# Awesome-Shield-0_5.net
KiCad netlist of a schematic drawn in EAGLE
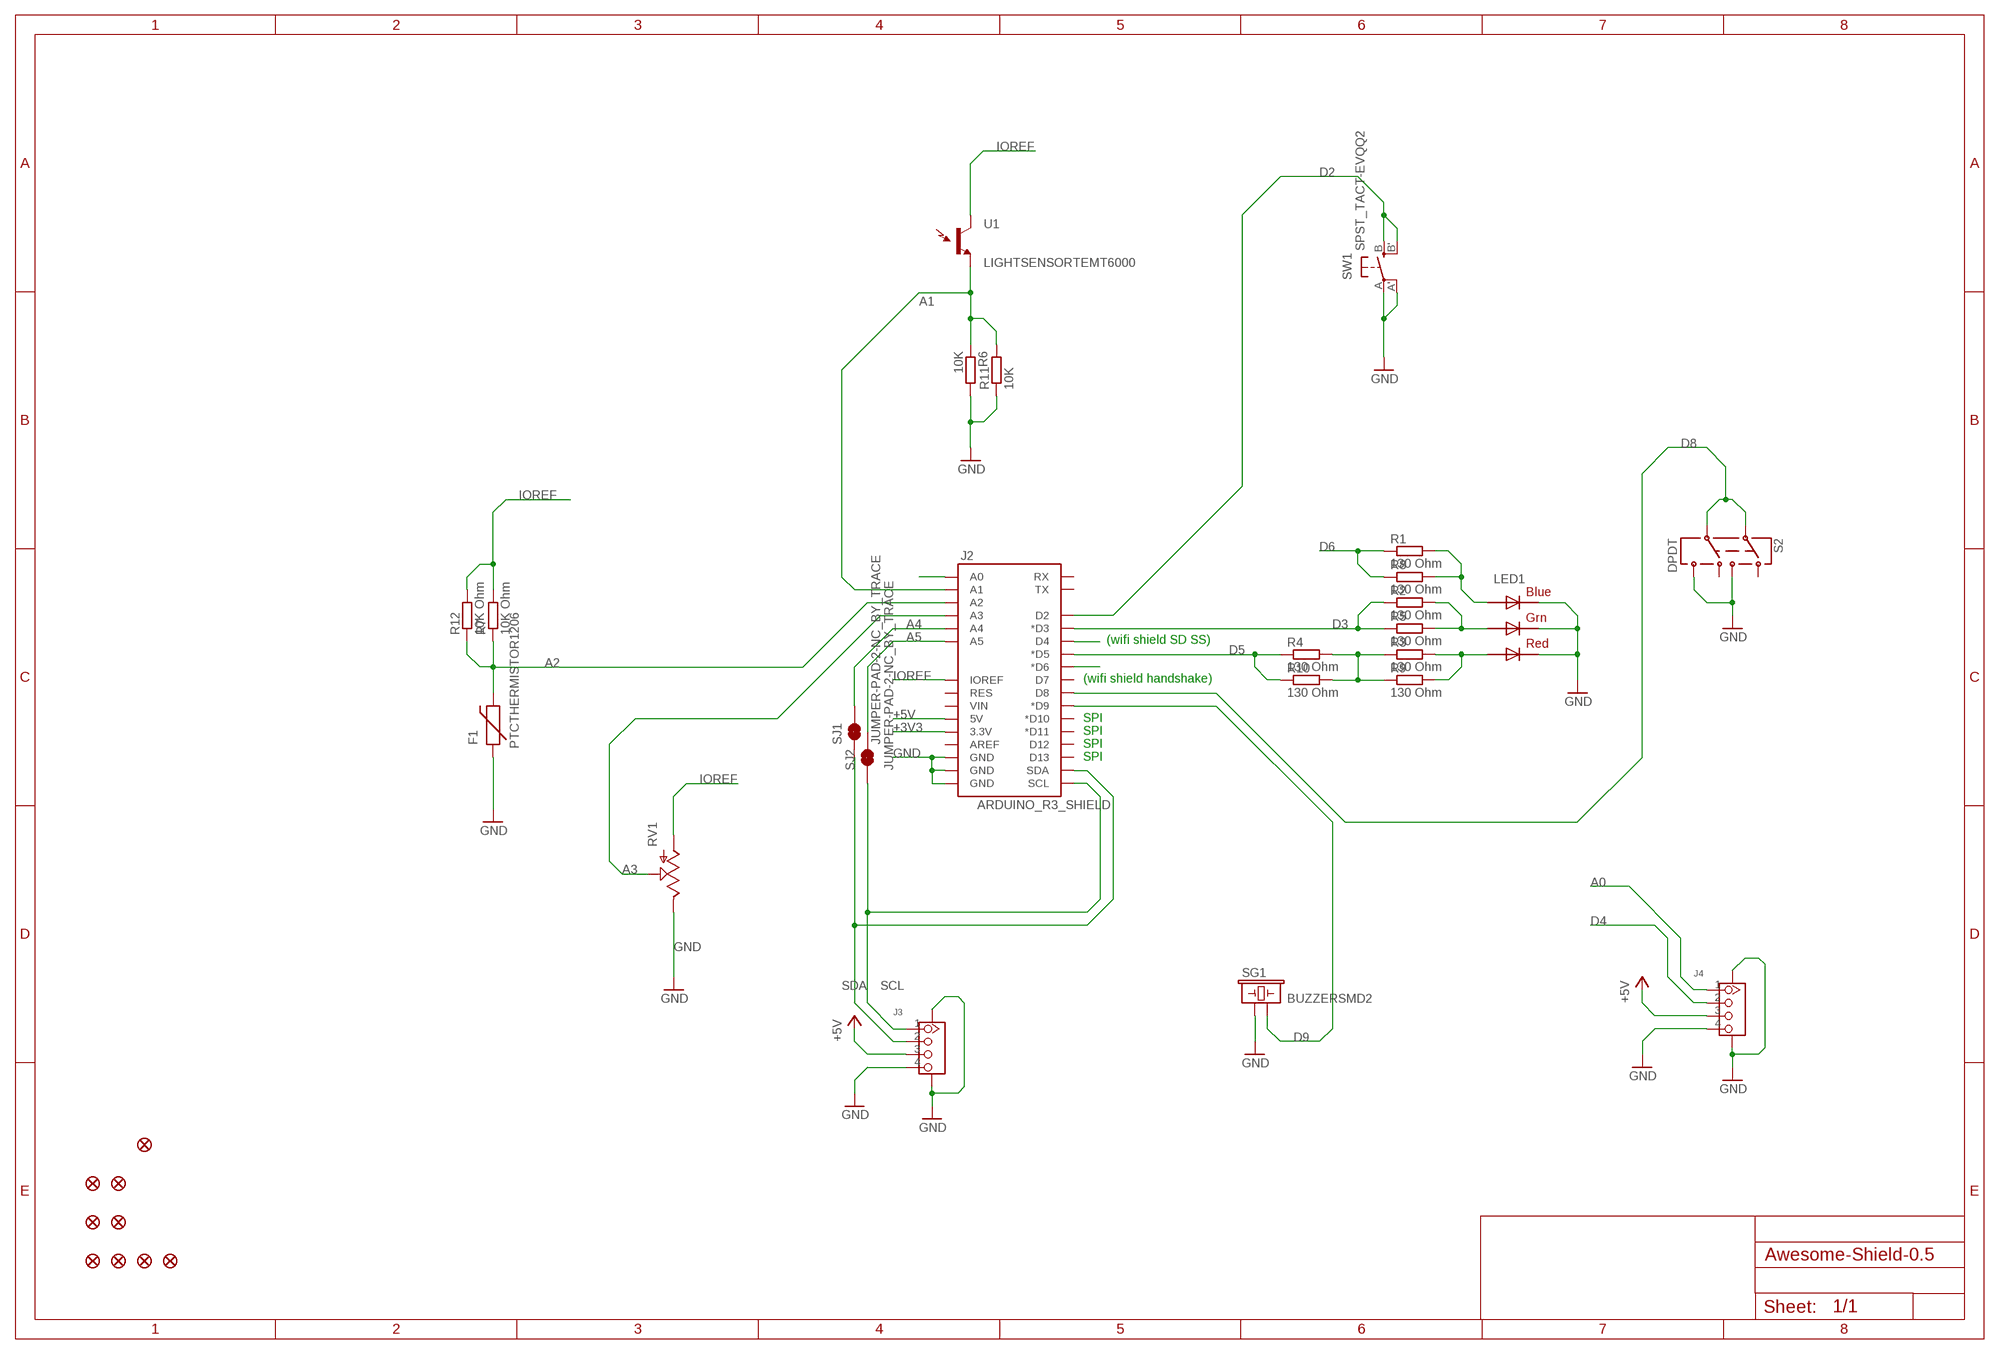
[diagram p0: schematic, sheet 1]

(export (version "E")
  (design (tool "Eeschema 10.0.6"))
  (components
    (comp (ref "F1")
      (value "PTCTHERMISTOR1206")
      (footprint "eagle-import:PTC-1206")
      (libsource (lib "eagle-import") (part "PTCTHERMISTOR1206"))
    )
    (comp (ref "FID1")
      (value "FIDUCIAL1X2")
      (footprint "eagle-import:FIDUCIAL-1X2")
      (libsource (lib "eagle-import") (part "FIDUCIAL1X2"))
    )
    (comp (ref "FID2")
      (value "FIDUCIAL1X2")
      (footprint "eagle-import:FIDUCIAL-1X2")
      (libsource (lib "eagle-import") (part "FIDUCIAL1X2"))
    )
    (comp (ref "FID3")
      (value "FIDUCIAL1X2")
      (footprint "eagle-import:FIDUCIAL-1X2")
      (libsource (lib "eagle-import") (part "FIDUCIAL1X2"))
    )
    (comp (ref "FID4")
      (value "FIDUCIAL1X2")
      (footprint "eagle-import:FIDUCIAL-1X2")
      (libsource (lib "eagle-import") (part "FIDUCIAL1X2"))
    )
    (comp (ref "FID5")
      (value "FIDUCIALUFIDUCIAL")
      (footprint "eagle-import:MICRO-FIDUCIAL")
      (libsource (lib "eagle-import") (part "FIDUCIALUFIDUCIAL"))
    )
    (comp (ref "FID6")
      (value "FIDUCIALUFIDUCIAL")
      (footprint "eagle-import:MICRO-FIDUCIAL")
      (libsource (lib "eagle-import") (part "FIDUCIALUFIDUCIAL"))
    )
    (comp (ref "FID9")
      (value "FIDUCIALUFIDUCIAL")
      (footprint "eagle-import:MICRO-FIDUCIAL")
      (libsource (lib "eagle-import") (part "FIDUCIALUFIDUCIAL"))
    )
    (comp (ref "FID10")
      (value "FIDUCIALUFIDUCIAL")
      (footprint "eagle-import:MICRO-FIDUCIAL")
      (libsource (lib "eagle-import") (part "FIDUCIALUFIDUCIAL"))
    )
    (comp (ref "FID15")
      (value "FIDUCIALUFIDUCIAL")
      (footprint "eagle-import:MICRO-FIDUCIAL")
      (libsource (lib "eagle-import") (part "FIDUCIALUFIDUCIAL"))
    )
    (comp (ref "J2")
      (value "ARDUINO_R3_SHIELD")
      (footprint "eagle-import:UNO_R3_SHIELD")
      (libsource (lib "eagle-import") (part "ARDUINO_R3_SHIELD"))
    )
    (comp (ref "J3")
      (value "GROVE-CONNECTOR-SMD(4+2P-2.0)")
      (footprint "eagle-import:HW4-SMD-2.0")
      (libsource (lib "eagle-import") (part "GROVE-CONNECTOR-SMD(4+2P-2.0)"))
    )
    (comp (ref "J4")
      (value "GROVE-CONNECTOR-SMD(4+2P-2.0)")
      (footprint "eagle-import:HW4-SMD-2.0")
      (libsource (lib "eagle-import") (part "GROVE-CONNECTOR-SMD(4+2P-2.0)"))
    )
    (comp (ref "LED1")
      (value "RGBLED5050")
      (footprint "eagle-import:RGBLED5050")
      (libsource (lib "eagle-import") (part "RGBLED5050"))
    )
    (comp (ref "R1")
      (value "130 Ohm")
      (footprint "eagle-import:R1206")
      (libsource (lib "eagle-import") (part "R-EU_R1206"))
    )
    (comp (ref "R2")
      (value "130 Ohm")
      (footprint "eagle-import:R1206")
      (libsource (lib "eagle-import") (part "R-EU_R1206"))
    )
    (comp (ref "R3")
      (value "130 Ohm")
      (footprint "eagle-import:R1206")
      (libsource (lib "eagle-import") (part "R-EU_R1206"))
    )
    (comp (ref "R4")
      (value "130 Ohm")
      (footprint "eagle-import:R1206")
      (libsource (lib "eagle-import") (part "R-EU_R1206"))
    )
    (comp (ref "R5")
      (value "130 Ohm")
      (footprint "eagle-import:R0603")
      (libsource (lib "eagle-import") (part "R-EU_R0603"))
    )
    (comp (ref "R6")
      (value "10K")
      (footprint "eagle-import:R1206")
      (libsource (lib "eagle-import") (part "R-EU_R1206"))
    )
    (comp (ref "R7")
      (value "10K Ohm")
      (footprint "eagle-import:R1206")
      (libsource (lib "eagle-import") (part "R-EU_R1206"))
    )
    (comp (ref "R8")
      (value "130 Ohm")
      (footprint "eagle-import:R0603")
      (libsource (lib "eagle-import") (part "R-EU_R0603"))
    )
    (comp (ref "R9")
      (value "130 Ohm")
      (footprint "eagle-import:R0603")
      (libsource (lib "eagle-import") (part "R-EU_R0603"))
    )
    (comp (ref "R10")
      (value "130 Ohm")
      (footprint "eagle-import:R0603")
      (libsource (lib "eagle-import") (part "R-EU_R0603"))
    )
    (comp (ref "R11")
      (value "10K")
      (footprint "eagle-import:R0603")
      (libsource (lib "eagle-import") (part "R-EU_R0603"))
    )
    (comp (ref "R12")
      (value "10K Ohm")
      (footprint "eagle-import:R0603")
      (libsource (lib "eagle-import") (part "R-EU_R0603"))
    )
    (comp (ref "RV1")
      (value "POT")
      (footprint "eagle-import:ALPS_POT")
      (libsource (lib "eagle-import") (part "POT"))
    )
    (comp (ref "S2")
      (value "DPDT")
      (footprint "eagle-import:AYZ0202")
      (libsource (lib "eagle-import") (part "SWITCH-DPDTAYZ0202"))
    )
    (comp (ref "SG1")
      (value "BUZZERSMD2")
      (footprint "eagle-import:BUZZER-CCV")
      (libsource (lib "eagle-import") (part "BUZZERSMD2"))
    )
    (comp (ref "SJ1")
      (value "JUMPER-PAD-2-NC_BY_TRACE")
      (footprint "eagle-import:PAD-JUMPER-2-NC_BY_TRACE_YES_SILK")
      (libsource (lib "eagle-import") (part "JUMPER-PAD-2-NC_BY_TRACE"))
    )
    (comp (ref "SJ2")
      (value "JUMPER-PAD-2-NC_BY_TRACE")
      (footprint "eagle-import:PAD-JUMPER-2-NC_BY_TRACE_YES_SILK")
      (libsource (lib "eagle-import") (part "JUMPER-PAD-2-NC_BY_TRACE"))
    )
    (comp (ref "SW1")
      (value "SPST_TACT-EVQQ2")
      (footprint "eagle-import:EVQ-Q2")
      (libsource (lib "eagle-import") (part "SPST_TACT-EVQQ2"))
    )
    (comp (ref "U1")
      (value "LIGHTSENSORTEMT6000")
      (footprint "eagle-import:TEMT6000-SEN")
      (libsource (lib "eagle-import") (part "LIGHTSENSORTEMT6000"))
    )
  )
  (nets
    (net (code "1") (name "+5V") (class "Default")
      (node (ref "J2") (pin "5V") (pinfunction "5V_5V") (pintype "bidirectional"))
      (node (ref "J3") (pin "3") (pinfunction "3_3") (pintype "bidirectional"))
      (node (ref "J4") (pin "3") (pinfunction "3_3") (pintype "bidirectional"))
    )
    (net (code "2") (name "/+3V3") (class "Default")
      (node (ref "J2") (pin "3.3V") (pinfunction "3.3V_3.3V") (pintype "bidirectional"))
    )
    (net (code "3") (name "/A0") (class "Default")
      (node (ref "J2") (pin "A0") (pinfunction "A0_A0") (pintype "bidirectional"))
      (node (ref "J4") (pin "1") (pinfunction "1_1") (pintype "bidirectional"))
    )
    (net (code "4") (name "/A1") (class "Default")
      (node (ref "J2") (pin "A1") (pinfunction "A1_A1") (pintype "bidirectional"))
      (node (ref "R11") (pin "2") (pinfunction "2_2") (pintype "passive"))
      (node (ref "R6") (pin "1") (pinfunction "1_1") (pintype "passive"))
      (node (ref "U1") (pin "EMITTER") (pinfunction "E1_EMITTER") (pintype "passive"))
    )
    (net (code "5") (name "/A2") (class "Default")
      (node (ref "F1") (pin "2") (pinfunction "2_2") (pintype "bidirectional"))
      (node (ref "J2") (pin "A2") (pinfunction "A2_A2") (pintype "bidirectional"))
      (node (ref "R12") (pin "1") (pinfunction "1_1") (pintype "passive"))
      (node (ref "R7") (pin "1") (pinfunction "1_1") (pintype "passive"))
    )
    (net (code "6") (name "/A3") (class "Default")
      (node (ref "J2") (pin "A3") (pinfunction "A3_A3") (pintype "bidirectional"))
      (node (ref "RV1") (pin "P$2") (pinfunction "S_P$2") (pintype "passive"))
    )
    (net (code "7") (name "/A4") (class "Default")
      (node (ref "J2") (pin "A4") (pinfunction "A4_A4") (pintype "bidirectional"))
      (node (ref "SJ1") (pin "2") (pinfunction "2_2") (pintype "passive"))
    )
    (net (code "8") (name "/A5") (class "Default")
      (node (ref "J2") (pin "A5") (pinfunction "A5_A5") (pintype "bidirectional"))
      (node (ref "SJ2") (pin "2") (pinfunction "2_2") (pintype "passive"))
    )
    (net (code "9") (name "/D2") (class "Default")
      (node (ref "J2") (pin "D2") (pinfunction "D2_D2") (pintype "bidirectional"))
      (node (ref "SW1") (pin "B") (pinfunction "S_B") (pintype "passive"))
      (node (ref "SW1") (pin "B'") (pinfunction "S1_B'") (pintype "passive"))
    )
    (net (code "10") (name "/D3") (class "Default")
      (node (ref "J2") (pin "D3") (pinfunction "*D3_D3") (pintype "bidirectional"))
      (node (ref "R2") (pin "1") (pinfunction "1_1") (pintype "passive"))
      (node (ref "R5") (pin "1") (pinfunction "1_1") (pintype "passive"))
    )
    (net (code "11") (name "/D4") (class "Default")
      (node (ref "J2") (pin "D4") (pinfunction "D4_D4") (pintype "bidirectional"))
      (node (ref "J4") (pin "2") (pinfunction "2_2") (pintype "bidirectional"))
    )
    (net (code "12") (name "/D5") (class "Default")
      (node (ref "J2") (pin "D5") (pinfunction "*D5_D5") (pintype "bidirectional"))
      (node (ref "R10") (pin "1") (pinfunction "1_1") (pintype "passive"))
      (node (ref "R4") (pin "1") (pinfunction "1_1") (pintype "passive"))
    )
    (net (code "13") (name "/D6") (class "Default")
      (node (ref "J2") (pin "D6") (pinfunction "*D6_D6") (pintype "bidirectional"))
      (node (ref "R1") (pin "1") (pinfunction "1_1") (pintype "passive"))
      (node (ref "R8") (pin "1") (pinfunction "1_1") (pintype "passive"))
    )
    (net (code "14") (name "/D8") (class "Default")
      (node (ref "J2") (pin "D8") (pinfunction "D8_D8") (pintype "bidirectional"))
      (node (ref "S2") (pin "2") (pinfunction "2_2") (pintype "bidirectional"))
      (node (ref "S2") (pin "5") (pinfunction "5_5") (pintype "bidirectional"))
    )
    (net (code "15") (name "/D9") (class "Default")
      (node (ref "J2") (pin "D9") (pinfunction "*D9_D9") (pintype "bidirectional"))
      (node (ref "SG1") (pin "-") (pinfunction "2_-") (pintype "passive"))
    )
    (net (code "16") (name "/IOREF") (class "Default")
      (node (ref "J2") (pin "IOREF") (pinfunction "IOREF_IOREF") (pintype "bidirectional"))
      (node (ref "R12") (pin "2") (pinfunction "2_2") (pintype "passive"))
      (node (ref "R7") (pin "2") (pinfunction "2_2") (pintype "passive"))
      (node (ref "RV1") (pin "P$3") (pinfunction "A_P$3") (pintype "passive"))
      (node (ref "U1") (pin "COLLECTOR") (pinfunction "C1_COLLECTOR") (pintype "passive"))
    )
    (net (code "17") (name "/SCL") (class "Default")
      (node (ref "J2") (pin "SCL") (pinfunction "SCL_SCL") (pintype "bidirectional"))
      (node (ref "J3") (pin "1") (pinfunction "1_1") (pintype "bidirectional"))
      (node (ref "SJ2") (pin "1") (pinfunction "1_1") (pintype "passive"))
    )
    (net (code "18") (name "/SDA") (class "Default")
      (node (ref "J2") (pin "SDA") (pinfunction "SDA_SDA") (pintype "bidirectional"))
      (node (ref "J3") (pin "2") (pinfunction "2_2") (pintype "bidirectional"))
      (node (ref "SJ1") (pin "1") (pinfunction "1_1") (pintype "passive"))
    )
    (net (code "19") (name "GND") (class "Default")
      (node (ref "F1") (pin "1") (pinfunction "1_1") (pintype "bidirectional"))
      (node (ref "J2") (pin "GND@0") (pinfunction "GND_GND@0") (pintype "bidirectional"))
      (node (ref "J2") (pin "GND@1") (pinfunction "GND_GND@1") (pintype "bidirectional"))
      (node (ref "J2") (pin "GND@2") (pinfunction "GND_GND@2") (pintype "bidirectional"))
      (node (ref "J3") (pin "4") (pinfunction "4_4") (pintype "bidirectional"))
      (node (ref "J3") (pin "SS1") (pinfunction "SS1_SS1") (pintype "bidirectional"))
      (node (ref "J3") (pin "SS2") (pinfunction "SS2_SS2") (pintype "bidirectional"))
      (node (ref "J4") (pin "4") (pinfunction "4_4") (pintype "bidirectional"))
      (node (ref "J4") (pin "SS1") (pinfunction "SS1_SS1") (pintype "bidirectional"))
      (node (ref "J4") (pin "SS2") (pinfunction "SS2_SS2") (pintype "bidirectional"))
      (node (ref "LED1") (pin "4") (pinfunction "BLUE_C_4") (pintype "bidirectional"))
      (node (ref "LED1") (pin "5") (pinfunction "RED_C_5") (pintype "bidirectional"))
      (node (ref "LED1") (pin "6") (pinfunction "GREEN_C_6") (pintype "bidirectional"))
      (node (ref "R11") (pin "1") (pinfunction "1_1") (pintype "passive"))
      (node (ref "R6") (pin "2") (pinfunction "2_2") (pintype "passive"))
      (node (ref "RV1") (pin "P$1") (pinfunction "E_P$1") (pintype "passive"))
      (node (ref "S2") (pin "3") (pinfunction "3_3") (pintype "bidirectional"))
      (node (ref "S2") (pin "6") (pinfunction "6_6") (pintype "bidirectional"))
      (node (ref "SG1") (pin "+") (pinfunction "1_+") (pintype "passive"))
      (node (ref "SW1") (pin "A") (pinfunction "P_A") (pintype "passive"))
      (node (ref "SW1") (pin "A'") (pinfunction "P1_A'") (pintype "passive"))
    )
    (net (code "20") (name "Net-(LED1-BLUE_A)") (class "Default")
      (node (ref "LED1") (pin "3") (pinfunction "BLUE_A_3") (pintype "bidirectional"))
      (node (ref "R1") (pin "2") (pinfunction "2_2") (pintype "passive"))
      (node (ref "R8") (pin "2") (pinfunction "2_2") (pintype "passive"))
    )
    (net (code "21") (name "Net-(LED1-GREEN_A)") (class "Default")
      (node (ref "LED1") (pin "1") (pinfunction "GREEN_A_1") (pintype "bidirectional"))
      (node (ref "R2") (pin "2") (pinfunction "2_2") (pintype "passive"))
      (node (ref "R5") (pin "2") (pinfunction "2_2") (pintype "passive"))
    )
    (net (code "22") (name "Net-(LED1-RED_A)") (class "Default")
      (node (ref "LED1") (pin "2") (pinfunction "RED_A_2") (pintype "bidirectional"))
      (node (ref "R3") (pin "2") (pinfunction "2_2") (pintype "passive"))
      (node (ref "R9") (pin "2") (pinfunction "2_2") (pintype "passive"))
    )
    (net (code "23") (name "Net-(R10-Pad2)") (class "Default")
      (node (ref "R10") (pin "2") (pinfunction "2_2") (pintype "passive"))
      (node (ref "R3") (pin "1") (pinfunction "1_1") (pintype "passive"))
      (node (ref "R4") (pin "2") (pinfunction "2_2") (pintype "passive"))
      (node (ref "R9") (pin "1") (pinfunction "1_1") (pintype "passive"))
    )
    (net (code "24") (name "unconnected-(J2-*D10-PadD10)") (class "Default")
      (node (ref "J2") (pin "D10") (pinfunction "*D10_D10") (pintype "bidirectional"))
    )
    (net (code "25") (name "unconnected-(J2-*D11-PadD11)") (class "Default")
      (node (ref "J2") (pin "D11") (pinfunction "*D11_D11") (pintype "bidirectional"))
    )
    (net (code "26") (name "unconnected-(J2-PadAREF)") (class "Default")
      (node (ref "J2") (pin "AREF") (pinfunction "AREF_AREF") (pintype "bidirectional"))
    )
    (net (code "27") (name "unconnected-(J2-PadD7)") (class "Default")
      (node (ref "J2") (pin "D7") (pinfunction "D7_D7") (pintype "bidirectional"))
    )
    (net (code "28") (name "unconnected-(J2-PadD12)") (class "Default")
      (node (ref "J2") (pin "D12") (pinfunction "D12_D12") (pintype "bidirectional"))
    )
    (net (code "29") (name "unconnected-(J2-PadD13)") (class "Default")
      (node (ref "J2") (pin "D13") (pinfunction "D13_D13") (pintype "bidirectional"))
    )
    (net (code "30") (name "unconnected-(J2-PadRES)") (class "Default")
      (node (ref "J2") (pin "RES") (pinfunction "RES_RES") (pintype "bidirectional"))
    )
    (net (code "31") (name "unconnected-(J2-PadRX)") (class "Default")
      (node (ref "J2") (pin "RX") (pinfunction "RX_RX") (pintype "bidirectional"))
    )
    (net (code "32") (name "unconnected-(J2-PadTX)") (class "Default")
      (node (ref "J2") (pin "TX") (pinfunction "TX_TX") (pintype "bidirectional"))
    )
    (net (code "33") (name "unconnected-(J2-PadVIN)") (class "Default")
      (node (ref "J2") (pin "VIN") (pinfunction "VIN_VIN") (pintype "bidirectional"))
    )
    (net (code "34") (name "unconnected-(S2-Pad1)") (class "Default")
      (node (ref "S2") (pin "1") (pinfunction "1_1") (pintype "bidirectional"))
    )
    (net (code "35") (name "unconnected-(S2-Pad4)") (class "Default")
      (node (ref "S2") (pin "4") (pinfunction "4_4") (pintype "bidirectional"))
    )
  )
)
